# Sheet3.net
KiCad netlist of a schematic drawn in Altium Designer
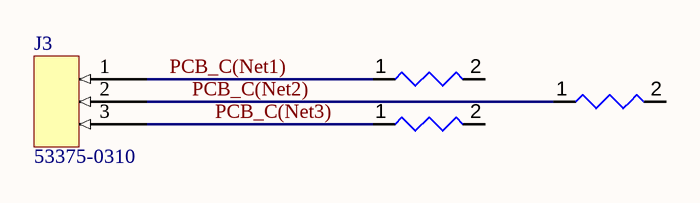
[diagram p0: Sheet3.SchDoc]

(export (version "E")
  (design (tool "Eeschema 10.0.6"))
  (components
    (comp (ref "J3")
      (value "53375-0310")
      (footprint "PCB1:SOJ127P870X356-20M")
      (fields (field (name "MANUFACTURER") "Molex"))
      (libsource (lib "SCH") (part "CMP-002-00074-2"))
    )
    (comp (ref "R1")
      (value "Resistor 10k +/-1% 1206 250 mW")
      (footprint "RESC3216X60X45ML15T20")
      (description "Chip Resistor, 10 KOhm, +/- 1%, 0.25 W, -55 to 155 degC, 1206 (3216 Metric)")
      (fields (field (name "TOLERANCE") "1%") (field (name "POWER") "250mW"))
      (libsource (lib "SCH") (part "RES-2"))
    )
    (comp (ref "R2")
      (value "Resistor 10k +/-1% 1206 250 mW")
      (footprint "RESC3216X60X45ML15T20")
      (description "Chip Resistor, 10 KOhm, +/- 1%, 0.25 W, -55 to 155 degC, 1206 (3216 Metric)")
      (fields (field (name "TOLERANCE") "1%") (field (name "POWER") "250mW"))
      (libsource (lib "SCH") (part "RES-2"))
    )
    (comp (ref "R3")
      (value "Resistor 10k +/-1% 1206 250 mW")
      (footprint "RESC3216X60X45ML15T20")
      (description "Chip Resistor, 10 KOhm, +/- 1%, 0.25 W, -55 to 155 degC, 1206 (3216 Metric)")
      (fields (field (name "TOLERANCE") "1%") (field (name "POWER") "250mW"))
      (libsource (lib "SCH") (part "RES-2"))
    )
  )
  (nets
    (net (code "1") (name "/PCB_C(Net1)") (class "Default")
      (node (ref "J3") (pin "1") (pinfunction "1_1") (pintype "input"))
      (node (ref "R1") (pin "1") (pinfunction "1_1") (pintype "passive"))
    )
    (net (code "2") (name "/PCB_C(Net2)") (class "Default")
      (node (ref "J3") (pin "2") (pinfunction "2_2") (pintype "input"))
      (node (ref "R2") (pin "1") (pinfunction "1_1") (pintype "passive"))
    )
    (net (code "3") (name "/PCB_C(Net3)") (class "Default")
      (node (ref "J3") (pin "3") (pinfunction "3_3") (pintype "input"))
      (node (ref "R3") (pin "1") (pinfunction "1_1") (pintype "passive"))
    )
    (net (code "4") (name "unconnected-(R1-Pad2)") (class "Default")
      (node (ref "R1") (pin "2") (pinfunction "2_2") (pintype "passive"))
    )
    (net (code "5") (name "unconnected-(R2-Pad2)") (class "Default")
      (node (ref "R2") (pin "2") (pinfunction "2_2") (pintype "passive"))
    )
    (net (code "6") (name "unconnected-(R3-Pad2)") (class "Default")
      (node (ref "R3") (pin "2") (pinfunction "2_2") (pintype "passive"))
    )
  )
)
